# 40khz_ultrasonic_receiver.net
KiCad netlist of a schematic drawn in EAGLE
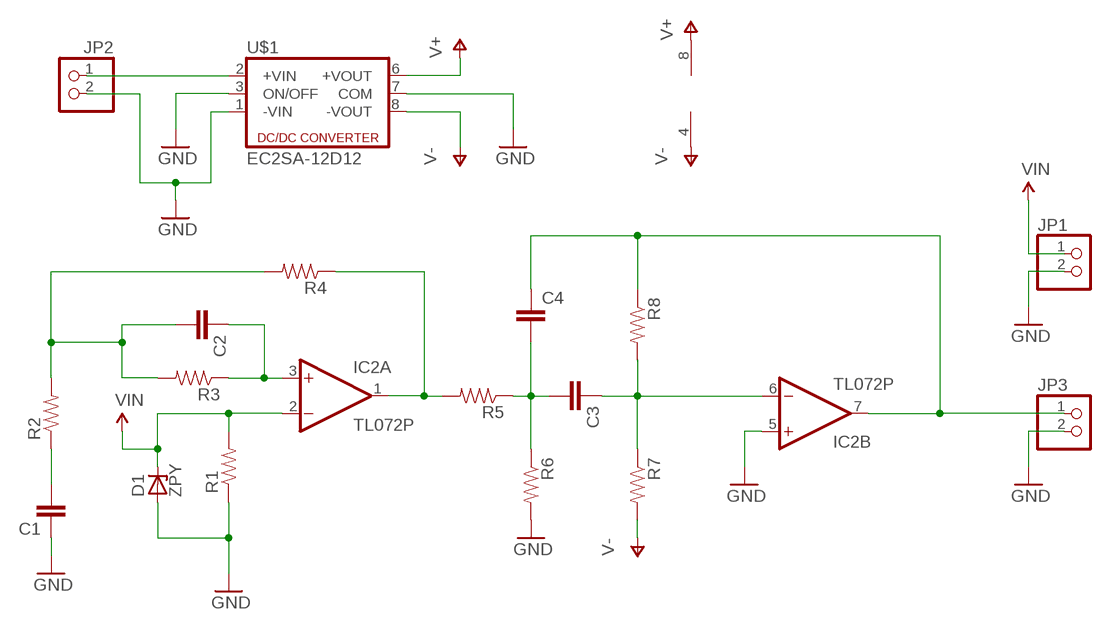
[diagram p0: schematic, sheet 1]

(export (version "E")
  (design (tool "Eeschema 10.0.6"))
  (components
    (comp (ref "C1")
      (value "CAPPTH")
      (footprint "eagle-import:CAP-PTH-SMALL")
      (libsource (lib "eagle-import") (part "CAPPTH"))
    )
    (comp (ref "C2")
      (value "CAPPTH")
      (footprint "eagle-import:CAP-PTH-SMALL")
      (libsource (lib "eagle-import") (part "CAPPTH"))
    )
    (comp (ref "C3")
      (value "CAPPTH")
      (footprint "eagle-import:CAP-PTH-SMALL")
      (libsource (lib "eagle-import") (part "CAPPTH"))
    )
    (comp (ref "C4")
      (value "CAPPTH")
      (footprint "eagle-import:CAP-PTH-SMALL")
      (libsource (lib "eagle-import") (part "CAPPTH"))
    )
    (comp (ref "D1")
      (value "ZPY")
      (footprint "eagle-import:DO41Z10")
      (libsource (lib "eagle-import") (part "ZPY"))
    )
    (comp (ref "IC2")
      (value "TL072P")
      (footprint "eagle-import:DIL08")
      (libsource (lib "eagle-import") (part "TL072P"))
    )
    (comp (ref "JP1")
      (value "PINHD-1X2")
      (footprint "eagle-import:1X02")
      (libsource (lib "eagle-import") (part "PINHD-1X2"))
    )
    (comp (ref "JP2")
      (value "PINHD-1X2")
      (footprint "eagle-import:1X02")
      (libsource (lib "eagle-import") (part "PINHD-1X2"))
    )
    (comp (ref "JP3")
      (value "PINHD-1X2")
      (footprint "eagle-import:1X02")
      (libsource (lib "eagle-import") (part "PINHD-1X2"))
    )
    (comp (ref "R1")
      (value "RESISTORPTH-1/4W")
      (footprint "eagle-import:AXIAL-0.4")
      (libsource (lib "eagle-import") (part "RESISTORPTH-1/4W"))
    )
    (comp (ref "R2")
      (value "RESISTORPTH-1/4W")
      (footprint "eagle-import:AXIAL-0.4")
      (libsource (lib "eagle-import") (part "RESISTORPTH-1/4W"))
    )
    (comp (ref "R3")
      (value "RESISTORPTH-1/4W")
      (footprint "eagle-import:AXIAL-0.4")
      (libsource (lib "eagle-import") (part "RESISTORPTH-1/4W"))
    )
    (comp (ref "R4")
      (value "RESISTORPTH-1/4W")
      (footprint "eagle-import:AXIAL-0.4")
      (libsource (lib "eagle-import") (part "RESISTORPTH-1/4W"))
    )
    (comp (ref "R5")
      (value "RESISTORPTH-1/4W")
      (footprint "eagle-import:AXIAL-0.4")
      (libsource (lib "eagle-import") (part "RESISTORPTH-1/4W"))
    )
    (comp (ref "R6")
      (value "RESISTORPTH-1/4W")
      (footprint "eagle-import:AXIAL-0.4")
      (libsource (lib "eagle-import") (part "RESISTORPTH-1/4W"))
    )
    (comp (ref "R7")
      (value "RESISTORPTH-1/4W")
      (footprint "eagle-import:AXIAL-0.4")
      (libsource (lib "eagle-import") (part "RESISTORPTH-1/4W"))
    )
    (comp (ref "R8")
      (value "RESISTORPTH-1/4W")
      (footprint "eagle-import:AXIAL-0.4")
      (libsource (lib "eagle-import") (part "RESISTORPTH-1/4W"))
    )
    (comp (ref "U$1")
      (value "EC2SA-12D12")
      (footprint "eagle-import:EC2SA")
      (libsource (lib "eagle-import") (part "EC2SA-12D12"))
    )
  )
  (nets
    (net (code "1") (name "GND") (class "Default")
      (node (ref "C1") (pin "1") (pinfunction "1_1") (pintype "passive"))
      (node (ref "D1") (pin "A") (pinfunction "A_A") (pintype "passive"))
      (node (ref "IC2") (pin "5") (pinfunction "+IN_5") (pintype "input"))
      (node (ref "JP1") (pin "2") (pinfunction "2_2") (pintype "passive"))
      (node (ref "JP2") (pin "2") (pinfunction "2_2") (pintype "passive"))
      (node (ref "JP3") (pin "2") (pinfunction "2_2") (pintype "passive"))
      (node (ref "R1") (pin "P$1") (pinfunction "1_P$1") (pintype "passive"))
      (node (ref "R6") (pin "P$2") (pinfunction "2_P$2") (pintype "passive"))
      (node (ref "U$1") (pin "1") (pinfunction "-VIN_1") (pintype "passive"))
      (node (ref "U$1") (pin "3") (pinfunction "ON/OFF_3") (pintype "passive"))
      (node (ref "U$1") (pin "7") (pinfunction "COM_7") (pintype "passive"))
    )
    (net (code "2") (name "Net-(IC2A-+IN)") (class "Default")
      (node (ref "C2") (pin "1") (pinfunction "1_1") (pintype "passive"))
      (node (ref "IC2") (pin "3") (pinfunction "+IN_3") (pintype "input"))
      (node (ref "R3") (pin "P$1") (pinfunction "1_P$1") (pintype "passive"))
    )
    (net (code "3") (name "Net-(IC2A-OUT)") (class "Default")
      (node (ref "IC2") (pin "1") (pinfunction "OUT_1") (pintype "output"))
      (node (ref "R4") (pin "P$1") (pinfunction "1_P$1") (pintype "passive"))
      (node (ref "R5") (pin "P$2") (pinfunction "2_P$2") (pintype "passive"))
    )
    (net (code "4") (name "Net-(IC2B--IN)") (class "Default")
      (node (ref "C3") (pin "1") (pinfunction "1_1") (pintype "passive"))
      (node (ref "IC2") (pin "6") (pinfunction "-IN_6") (pintype "input"))
      (node (ref "R7") (pin "P$1") (pinfunction "1_P$1") (pintype "passive"))
      (node (ref "R8") (pin "P$2") (pinfunction "2_P$2") (pintype "passive"))
    )
    (net (code "5") (name "Net-(IC2B-OUT)") (class "Default")
      (node (ref "C4") (pin "1") (pinfunction "1_1") (pintype "passive"))
      (node (ref "IC2") (pin "7") (pinfunction "OUT_7") (pintype "output"))
      (node (ref "JP3") (pin "1") (pinfunction "1_1") (pintype "passive"))
      (node (ref "R8") (pin "P$1") (pinfunction "1_P$1") (pintype "passive"))
    )
    (net (code "6") (name "Net-(R2-1)") (class "Default")
      (node (ref "C1") (pin "2") (pinfunction "2_2") (pintype "passive"))
      (node (ref "R2") (pin "P$1") (pinfunction "1_P$1") (pintype "passive"))
    )
    (net (code "7") (name "Net-(R2-2)") (class "Default")
      (node (ref "C2") (pin "2") (pinfunction "2_2") (pintype "passive"))
      (node (ref "R2") (pin "P$2") (pinfunction "2_P$2") (pintype "passive"))
      (node (ref "R3") (pin "P$2") (pinfunction "2_P$2") (pintype "passive"))
      (node (ref "R4") (pin "P$2") (pinfunction "2_P$2") (pintype "passive"))
    )
    (net (code "8") (name "Net-(R5-1)") (class "Default")
      (node (ref "C3") (pin "2") (pinfunction "2_2") (pintype "passive"))
      (node (ref "C4") (pin "2") (pinfunction "2_2") (pintype "passive"))
      (node (ref "R5") (pin "P$1") (pinfunction "1_P$1") (pintype "passive"))
      (node (ref "R6") (pin "P$1") (pinfunction "1_P$1") (pintype "passive"))
    )
    (net (code "9") (name "Net-(U$1-+VIN)") (class "Default")
      (node (ref "JP2") (pin "1") (pinfunction "1_1") (pintype "passive"))
      (node (ref "U$1") (pin "2") (pinfunction "+VIN_2") (pintype "passive"))
    )
    (net (code "10") (name "V+") (class "Default")
      (node (ref "IC2") (pin "8") (pinfunction "V+_8") (pintype "power_in"))
      (node (ref "U$1") (pin "6") (pinfunction "+VOUT_6") (pintype "passive"))
    )
    (net (code "11") (name "V-") (class "Default")
      (node (ref "IC2") (pin "4") (pinfunction "V-_4") (pintype "power_in"))
      (node (ref "R7") (pin "P$2") (pinfunction "2_P$2") (pintype "passive"))
      (node (ref "U$1") (pin "8") (pinfunction "-VOUT_8") (pintype "passive"))
    )
    (net (code "12") (name "VIN") (class "Default")
      (node (ref "D1") (pin "C") (pinfunction "C_C") (pintype "passive"))
      (node (ref "IC2") (pin "2") (pinfunction "-IN_2") (pintype "input"))
      (node (ref "JP1") (pin "1") (pinfunction "1_1") (pintype "passive"))
      (node (ref "R1") (pin "P$2") (pinfunction "2_P$2") (pintype "passive"))
    )
  )
)
